# bldc_tach_schematic.net
KiCad netlist of a schematic drawn in EAGLE
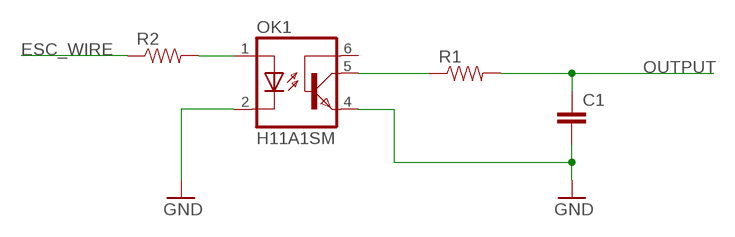
[diagram p0: schematic, sheet 1]

(export (version "E")
  (design (tool "Eeschema 10.0.6"))
  (components
    (comp (ref "C1")
      (value "CAP0603-CAP")
      (footprint "eagle-import:0603-CAP")
      (libsource (lib "eagle-import") (part "CAP0603-CAP"))
    )
    (comp (ref "OK1")
      (value "H11A1SM")
      (footprint "eagle-import:DIL6-SMD")
      (libsource (lib "eagle-import") (part "H11A?MS1"))
    )
    (comp (ref "R1")
      (value "RESISTOR0603-RES")
      (footprint "eagle-import:0603-RES")
      (libsource (lib "eagle-import") (part "RESISTOR0603-RES"))
    )
    (comp (ref "R2")
      (value "RESISTOR0603-RES")
      (footprint "eagle-import:0603-RES")
      (libsource (lib "eagle-import") (part "RESISTOR0603-RES"))
    )
  )
  (nets
    (net (code "1") (name "/ESC_WIRE") (class "Default")
      (node (ref "R2") (pin "1") (pinfunction "1_1") (pintype "passive"))
    )
    (net (code "2") (name "/OUTPUT") (class "Default")
      (node (ref "C1") (pin "1") (pinfunction "1_1") (pintype "passive"))
      (node (ref "R1") (pin "2") (pinfunction "2_2") (pintype "passive"))
    )
    (net (code "3") (name "GND") (class "Default")
      (node (ref "C1") (pin "2") (pinfunction "2_2") (pintype "passive"))
      (node (ref "OK1") (pin "2") (pinfunction "C_2") (pintype "passive"))
      (node (ref "OK1") (pin "4") (pinfunction "EMI_4") (pintype "passive"))
    )
    (net (code "4") (name "Net-(OK1-A)") (class "Default")
      (node (ref "OK1") (pin "1") (pinfunction "A_1") (pintype "passive"))
      (node (ref "R2") (pin "2") (pinfunction "2_2") (pintype "passive"))
    )
    (net (code "5") (name "Net-(OK1-COL)") (class "Default")
      (node (ref "OK1") (pin "5") (pinfunction "COL_5") (pintype "passive"))
      (node (ref "R1") (pin "1") (pinfunction "1_1") (pintype "passive"))
    )
    (net (code "6") (name "unconnected-(OK1-BAS-Pad6)") (class "Default")
      (node (ref "OK1") (pin "6") (pinfunction "BAS_6") (pintype "passive"))
    )
  )
)
